# rng1.net
KiCad netlist of a schematic drawn in EAGLE
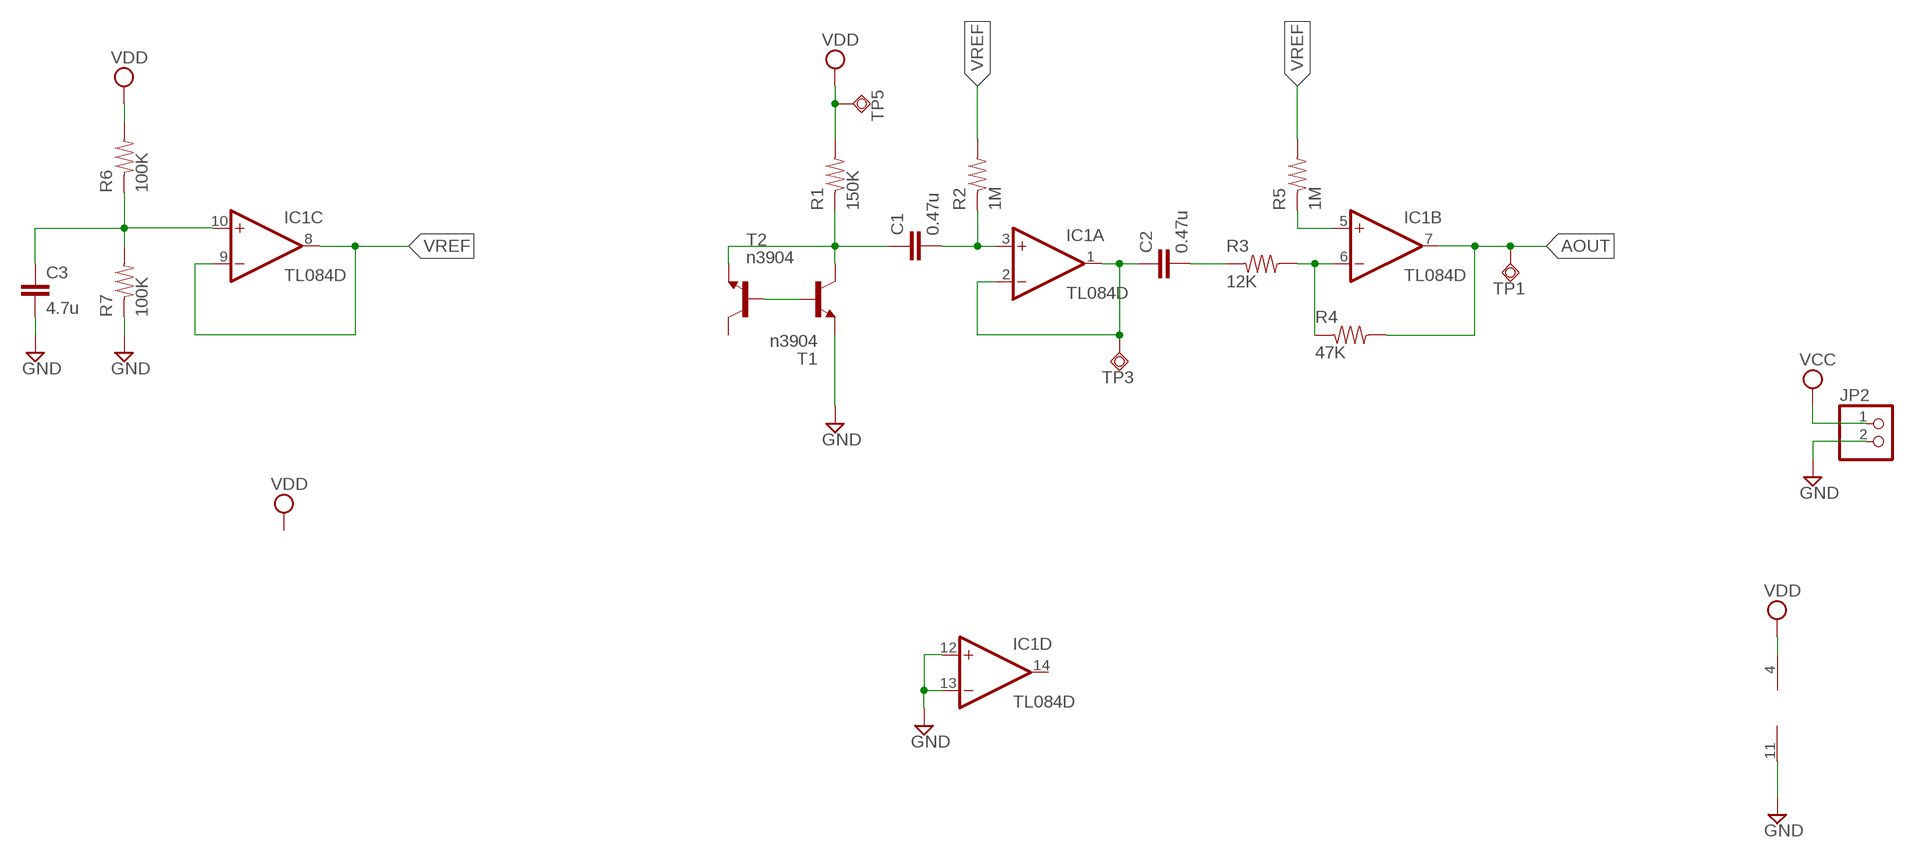
[diagram p0: schematic, sheet 1]
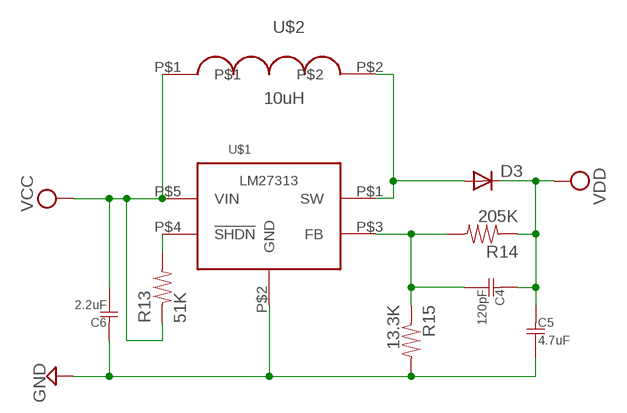
[diagram p1: schematic, sheet 2]

(export (version "E")
  (design (tool "Eeschema 10.0.6"))
  (components
    (comp (ref "C1")
      (value "0.47u")
      (footprint "eagle-import:C0805")
      (libsource (lib "eagle-import") (part "C-EUC0805"))
    )
    (comp (ref "C2")
      (value "0.47u")
      (footprint "eagle-import:C0805")
      (libsource (lib "eagle-import") (part "C-EUC0805"))
    )
    (comp (ref "C3")
      (value "4.7u")
      (footprint "eagle-import:C0805")
      (libsource (lib "eagle-import") (part "C-EUC0805"))
    )
    (comp (ref "IC1")
      (value "TL084D")
      (footprint "eagle-import:SO14")
      (libsource (lib "eagle-import") (part "TL084D"))
    )
    (comp (ref "JP2")
      (value "PINHD-1X2")
      (footprint "eagle-import:1X02")
      (libsource (lib "eagle-import") (part "PINHD-1X2"))
    )
    (comp (ref "R1")
      (value "150K")
      (footprint "eagle-import:R0805")
      (libsource (lib "eagle-import") (part "R0805"))
    )
    (comp (ref "R2")
      (value "1M")
      (footprint "eagle-import:R0805")
      (libsource (lib "eagle-import") (part "R0805"))
    )
    (comp (ref "R3")
      (value "12K")
      (footprint "eagle-import:R0805")
      (libsource (lib "eagle-import") (part "R0805"))
    )
    (comp (ref "R4")
      (value "47K")
      (footprint "eagle-import:R0805")
      (libsource (lib "eagle-import") (part "R0805"))
    )
    (comp (ref "R5")
      (value "1M")
      (footprint "eagle-import:R0805")
      (libsource (lib "eagle-import") (part "R0805"))
    )
    (comp (ref "R6")
      (value "100K")
      (footprint "eagle-import:R0805")
      (libsource (lib "eagle-import") (part "R0805"))
    )
    (comp (ref "R7")
      (value "100K")
      (footprint "eagle-import:R0805")
      (libsource (lib "eagle-import") (part "R0805"))
    )
    (comp (ref "T1")
      (value "n3904")
      (footprint "eagle-import:SOT23-BEC")
      (libsource (lib "eagle-import") (part "-NPN-SOT23-BECMMBT3904LT1"))
    )
    (comp (ref "T2")
      (value "n3904")
      (footprint "eagle-import:SOT23-BEC")
      (libsource (lib "eagle-import") (part "-NPN-SOT23-BECMMBT3904LT1"))
    )
    (comp (ref "TP1")
      (value "TPSQPAD1-13")
      (footprint "eagle-import:P1-13")
      (libsource (lib "eagle-import") (part "TPSQPAD1-13"))
    )
    (comp (ref "TP3")
      (value "TPSQPAD1-13")
      (footprint "eagle-import:P1-13")
      (libsource (lib "eagle-import") (part "TPSQPAD1-13"))
    )
    (comp (ref "TP5")
      (value "TPSQPAD1-13")
      (footprint "eagle-import:P1-13")
      (libsource (lib "eagle-import") (part "TPSQPAD1-13"))
    )
    (comp (ref "C4")
      (value "120pF")
      (footprint "eagle-import:R0805")
      (libsource (lib "eagle-import") (part "C0805"))
    )
    (comp (ref "C5")
      (value "4.7uF")
      (footprint "eagle-import:R0805")
      (libsource (lib "eagle-import") (part "C0805"))
    )
    (comp (ref "C6")
      (value "2.2uF")
      (footprint "eagle-import:R0805")
      (libsource (lib "eagle-import") (part "C0805"))
    )
    (comp (ref "D3")
      (value "DIODE-SOD123")
      (footprint "eagle-import:SOD123")
      (libsource (lib "eagle-import") (part "DIODE-SOD123"))
    )
    (comp (ref "R13")
      (value "51K")
      (footprint "eagle-import:R0805")
      (libsource (lib "eagle-import") (part "R0805"))
    )
    (comp (ref "R14")
      (value "205K")
      (footprint "eagle-import:R0805")
      (libsource (lib "eagle-import") (part "R0805"))
    )
    (comp (ref "R15")
      (value "13.3K")
      (footprint "eagle-import:R0805")
      (libsource (lib "eagle-import") (part "R0805"))
    )
    (comp (ref "U$1")
      (value "LM27313")
      (footprint "eagle-import:SOT-23-5")
      (libsource (lib "eagle-import") (part "LM27313"))
    )
    (comp (ref "U$2")
      (value "10uH")
      (footprint "eagle-import:L1007")
      (libsource (lib "eagle-import") (part "CB2518"))
    )
  )
  (nets
    (net (code "1") (name "AOUT") (class "Default")
      (node (ref "IC1") (pin "7") (pinfunction "OUT_7") (pintype "output"))
      (node (ref "R4") (pin "P$2") (pinfunction "2_P$2") (pintype "passive"))
      (node (ref "TP1") (pin "TP") (pinfunction "TP_TP") (pintype "input"))
    )
    (net (code "2") (name "GND") (class "Default")
      (node (ref "C3") (pin "2") (pinfunction "2_2") (pintype "passive"))
      (node (ref "C5") (pin "P$2") (pinfunction "2_P$2") (pintype "passive"))
      (node (ref "C6") (pin "P$1") (pinfunction "1_P$1") (pintype "passive"))
      (node (ref "IC1") (pin "11") (pinfunction "V-_11") (pintype "power_in"))
      (node (ref "IC1") (pin "12") (pinfunction "+IN_12") (pintype "input"))
      (node (ref "IC1") (pin "13") (pinfunction "-IN_13") (pintype "input"))
      (node (ref "JP2") (pin "2") (pinfunction "2_2") (pintype "passive"))
      (node (ref "R15") (pin "P$2") (pinfunction "2_P$2") (pintype "passive"))
      (node (ref "R7") (pin "P$1") (pinfunction "1_P$1") (pintype "passive"))
      (node (ref "T2") (pin "E") (pinfunction "E_E") (pintype "passive"))
      (node (ref "U$1") (pin "P$2") (pinfunction "GND_P$2") (pintype "power_in"))
    )
    (net (code "3") (name "Net-(C4-2)") (class "Default")
      (node (ref "C4") (pin "P$2") (pinfunction "2_P$2") (pintype "passive"))
      (node (ref "R14") (pin "P$2") (pinfunction "2_P$2") (pintype "passive"))
      (node (ref "R15") (pin "P$1") (pinfunction "1_P$1") (pintype "passive"))
      (node (ref "U$1") (pin "P$3") (pinfunction "FB_P$3") (pintype "bidirectional"))
    )
    (net (code "4") (name "Net-(IC1A-+IN)") (class "Default")
      (node (ref "C1") (pin "2") (pinfunction "2_2") (pintype "passive"))
      (node (ref "IC1") (pin "3") (pinfunction "+IN_3") (pintype "input"))
      (node (ref "R2") (pin "P$1") (pinfunction "1_P$1") (pintype "passive"))
    )
    (net (code "5") (name "Net-(IC1A--IN)") (class "Default")
      (node (ref "C2") (pin "1") (pinfunction "1_1") (pintype "passive"))
      (node (ref "IC1") (pin "1") (pinfunction "OUT_1") (pintype "output"))
      (node (ref "IC1") (pin "2") (pinfunction "-IN_2") (pintype "input"))
      (node (ref "TP3") (pin "TP") (pinfunction "TP_TP") (pintype "input"))
    )
    (net (code "6") (name "Net-(IC1B-+IN)") (class "Default")
      (node (ref "IC1") (pin "5") (pinfunction "+IN_5") (pintype "input"))
      (node (ref "R5") (pin "P$1") (pinfunction "1_P$1") (pintype "passive"))
    )
    (net (code "7") (name "Net-(IC1B--IN)") (class "Default")
      (node (ref "IC1") (pin "6") (pinfunction "-IN_6") (pintype "input"))
      (node (ref "R3") (pin "P$2") (pinfunction "2_P$2") (pintype "passive"))
      (node (ref "R4") (pin "P$1") (pinfunction "1_P$1") (pintype "passive"))
    )
    (net (code "8") (name "Net-(IC1C-+IN)") (class "Default")
      (node (ref "C3") (pin "1") (pinfunction "1_1") (pintype "passive"))
      (node (ref "IC1") (pin "10") (pinfunction "+IN_10") (pintype "input"))
      (node (ref "R6") (pin "P$1") (pinfunction "1_P$1") (pintype "passive"))
      (node (ref "R7") (pin "P$2") (pinfunction "2_P$2") (pintype "passive"))
    )
    (net (code "9") (name "Net-(R1-1)") (class "Default")
      (node (ref "C1") (pin "1") (pinfunction "1_1") (pintype "passive"))
      (node (ref "R1") (pin "P$1") (pinfunction "1_P$1") (pintype "passive"))
      (node (ref "T1") (pin "E") (pinfunction "E_E") (pintype "passive"))
      (node (ref "T2") (pin "C") (pinfunction "C_C") (pintype "passive"))
    )
    (net (code "10") (name "Net-(R3-1)") (class "Default")
      (node (ref "C2") (pin "2") (pinfunction "2_2") (pintype "passive"))
      (node (ref "R3") (pin "P$1") (pinfunction "1_P$1") (pintype "passive"))
    )
    (net (code "11") (name "Net-(R13-2)") (class "Default")
      (node (ref "R13") (pin "P$2") (pinfunction "2_P$2") (pintype "passive"))
      (node (ref "U$1") (pin "P$4") (pinfunction "~{SHDN}_P$4") (pintype "bidirectional"))
    )
    (net (code "12") (name "Net-(T1-PadB)") (class "Default")
      (node (ref "T1") (pin "B") (pinfunction "B_B") (pintype "passive"))
      (node (ref "T2") (pin "B") (pinfunction "B_B") (pintype "passive"))
    )
    (net (code "13") (name "Net-(U$1-SW)") (class "Default")
      (node (ref "D3") (pin "A") (pinfunction "A_A") (pintype "passive"))
      (node (ref "U$1") (pin "P$1") (pinfunction "SW_P$1") (pintype "bidirectional"))
      (node (ref "U$2") (pin "P$2") (pinfunction "P$2_P$2") (pintype "passive"))
    )
    (net (code "14") (name "VCC") (class "Default")
      (node (ref "C6") (pin "P$2") (pinfunction "2_P$2") (pintype "passive"))
      (node (ref "JP2") (pin "1") (pinfunction "1_1") (pintype "passive"))
      (node (ref "R13") (pin "P$1") (pinfunction "1_P$1") (pintype "passive"))
      (node (ref "U$1") (pin "P$5") (pinfunction "VIN_P$5") (pintype "power_in"))
      (node (ref "U$2") (pin "P$1") (pinfunction "P$1_P$1") (pintype "passive"))
    )
    (net (code "15") (name "VDD") (class "Default")
      (node (ref "C4") (pin "P$1") (pinfunction "1_P$1") (pintype "passive"))
      (node (ref "C5") (pin "P$1") (pinfunction "1_P$1") (pintype "passive"))
      (node (ref "D3") (pin "C") (pinfunction "C_C") (pintype "passive"))
      (node (ref "IC1") (pin "4") (pinfunction "V+_4") (pintype "power_in"))
      (node (ref "R1") (pin "P$2") (pinfunction "2_P$2") (pintype "passive"))
      (node (ref "R14") (pin "P$1") (pinfunction "1_P$1") (pintype "passive"))
      (node (ref "R6") (pin "P$2") (pinfunction "2_P$2") (pintype "passive"))
      (node (ref "TP5") (pin "TP") (pinfunction "TP_TP") (pintype "input"))
    )
    (net (code "16") (name "VREF") (class "Default")
      (node (ref "IC1") (pin "8") (pinfunction "OUT_8") (pintype "output"))
      (node (ref "IC1") (pin "9") (pinfunction "-IN_9") (pintype "input"))
      (node (ref "R2") (pin "P$2") (pinfunction "2_P$2") (pintype "passive"))
      (node (ref "R5") (pin "P$2") (pinfunction "2_P$2") (pintype "passive"))
    )
    (net (code "17") (name "unconnected-(IC1D-OUT-Pad14)") (class "Default")
      (node (ref "IC1") (pin "14") (pinfunction "OUT_14") (pintype "output"))
    )
    (net (code "18") (name "unconnected-(T1-PadC)") (class "Default")
      (node (ref "T1") (pin "C") (pinfunction "C_C") (pintype "passive"))
    )
  )
)
